# esp8285-router.net
KiCad netlist of a schematic drawn in EAGLE
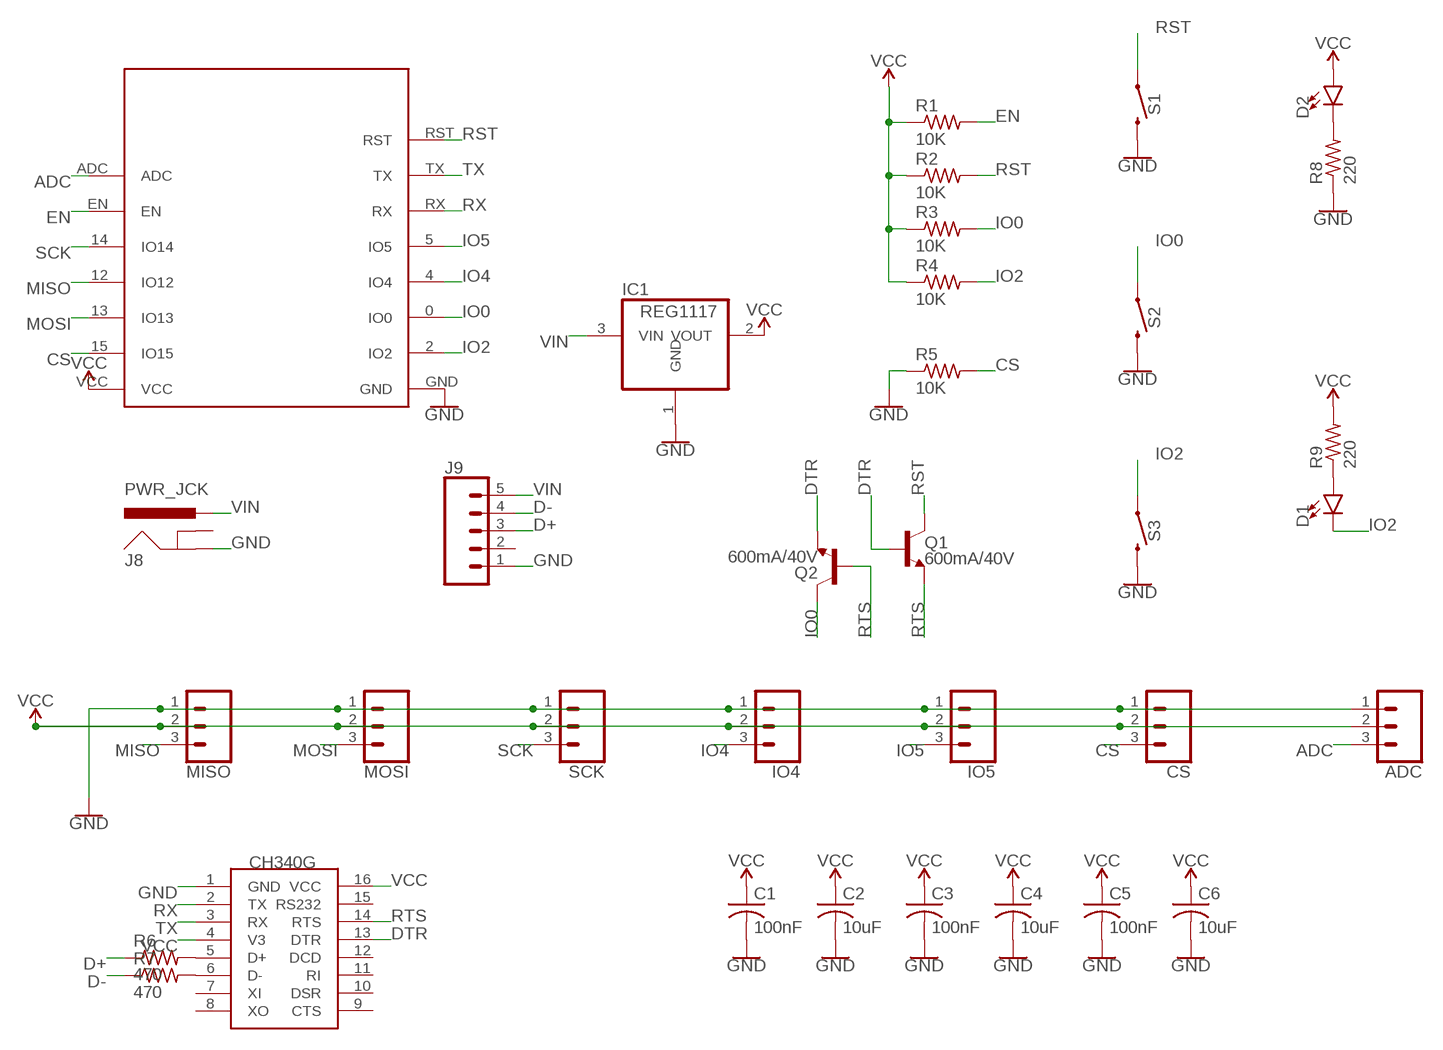
[diagram p0: schematic, sheet 1]

(export (version "E")
  (design (tool "Eeschema 10.0.6"))
  (components
    (comp (ref "ADC")
      (value "CONN_03")
      (footprint "eagle-import:1X03")
      (libsource (lib "eagle-import") (part "CONN_03"))
    )
    (comp (ref "C1")
      (value "100nF")
      (footprint "eagle-import:C1206")
      (libsource (lib "eagle-import") (part "C-USC1206"))
    )
    (comp (ref "C2")
      (value "10uF")
      (footprint "eagle-import:C1206")
      (libsource (lib "eagle-import") (part "C-USC1206"))
    )
    (comp (ref "C3")
      (value "100nF")
      (footprint "eagle-import:C1206")
      (libsource (lib "eagle-import") (part "C-USC1206"))
    )
    (comp (ref "C4")
      (value "10uF")
      (footprint "eagle-import:C1206")
      (libsource (lib "eagle-import") (part "C-USC1206"))
    )
    (comp (ref "C5")
      (value "100nF")
      (footprint "eagle-import:C1206")
      (libsource (lib "eagle-import") (part "C-USC1206"))
    )
    (comp (ref "C6")
      (value "10uF")
      (footprint "eagle-import:C1206")
      (libsource (lib "eagle-import") (part "C-USC1206"))
    )
    (comp (ref "CH340C")
      (value "CH340C")
      (footprint "eagle-import:SOIC16")
      (libsource (lib "eagle-import") (part "CH340G"))
    )
    (comp (ref "CS")
      (value "CONN_03")
      (footprint "eagle-import:1X03")
      (libsource (lib "eagle-import") (part "CONN_03"))
    )
    (comp (ref "D1")
      (value "LED1206")
      (footprint "eagle-import:LED-1206")
      (libsource (lib "eagle-import") (part "LED1206"))
    )
    (comp (ref "D2")
      (value "LED1206")
      (footprint "eagle-import:LED-1206")
      (libsource (lib "eagle-import") (part "LED1206"))
    )
    (comp (ref "IC1")
      (value "REG1117")
      (footprint "eagle-import:SOT223")
      (libsource (lib "eagle-import") (part "REG1117"))
    )
    (comp (ref "IO4")
      (value "CONN_03")
      (footprint "eagle-import:1X03")
      (libsource (lib "eagle-import") (part "CONN_03"))
    )
    (comp (ref "IO5")
      (value "CONN_03")
      (footprint "eagle-import:1X03")
      (libsource (lib "eagle-import") (part "CONN_03"))
    )
    (comp (ref "J8")
      (value "PWR_JCK")
      (footprint "eagle-import:POWER_JACK_SLOT")
      (libsource (lib "eagle-import") (part "POWER_JACKSLT"))
    )
    (comp (ref "J9")
      (value "CONN_05")
      (footprint "eagle-import:1X05")
      (libsource (lib "eagle-import") (part "CONN_05"))
    )
    (comp (ref "MISO")
      (value "CONN_03")
      (footprint "eagle-import:1X03")
      (libsource (lib "eagle-import") (part "CONN_03"))
    )
    (comp (ref "MOSI")
      (value "CONN_03")
      (footprint "eagle-import:1X03")
      (libsource (lib "eagle-import") (part "CONN_03"))
    )
    (comp (ref "Q1")
      (value "600mA/40V")
      (footprint "eagle-import:SOT23-3")
      (libsource (lib "eagle-import") (part "TRANS_NPN-MMBT2222AL"))
    )
    (comp (ref "Q2")
      (value "600mA/40V")
      (footprint "eagle-import:SOT23-3")
      (libsource (lib "eagle-import") (part "TRANS_NPN-MMBT2222AL"))
    )
    (comp (ref "R1")
      (value "10K")
      (footprint "eagle-import:R1206")
      (libsource (lib "eagle-import") (part "R-US_R1206"))
    )
    (comp (ref "R2")
      (value "10K")
      (footprint "eagle-import:R1206")
      (libsource (lib "eagle-import") (part "R-US_R1206"))
    )
    (comp (ref "R3")
      (value "10K")
      (footprint "eagle-import:R1206")
      (libsource (lib "eagle-import") (part "R-US_R1206"))
    )
    (comp (ref "R4")
      (value "10K")
      (footprint "eagle-import:R1206")
      (libsource (lib "eagle-import") (part "R-US_R1206"))
    )
    (comp (ref "R5")
      (value "10K")
      (footprint "eagle-import:R1206")
      (libsource (lib "eagle-import") (part "R-US_R1206"))
    )
    (comp (ref "R6")
      (value "470")
      (footprint "eagle-import:R1206")
      (libsource (lib "eagle-import") (part "R-US_R1206"))
    )
    (comp (ref "R7")
      (value "470")
      (footprint "eagle-import:R1206")
      (libsource (lib "eagle-import") (part "R-US_R1206"))
    )
    (comp (ref "R8")
      (value "220")
      (footprint "eagle-import:R1206")
      (libsource (lib "eagle-import") (part "R-US_R1206"))
    )
    (comp (ref "R9")
      (value "220")
      (footprint "eagle-import:R1206")
      (libsource (lib "eagle-import") (part "R-US_R1206"))
    )
    (comp (ref "S1")
      (value "MOMENTARY-SWITCH-SPST-PTH-6.0MM")
      (footprint "eagle-import:TACTILE_SWITCH_PTH_6.0MM")
      (libsource (lib "eagle-import") (part "MOMENTARY-SWITCH-SPST-PTH-6.0MM"))
    )
    (comp (ref "S2")
      (value "MOMENTARY-SWITCH-SPST-PTH-6.0MM")
      (footprint "eagle-import:TACTILE_SWITCH_PTH_6.0MM")
      (libsource (lib "eagle-import") (part "MOMENTARY-SWITCH-SPST-PTH-6.0MM"))
    )
    (comp (ref "S3")
      (value "MOMENTARY-SWITCH-SPST-PTH-6.0MM")
      (footprint "eagle-import:TACTILE_SWITCH_PTH_6.0MM")
      (libsource (lib "eagle-import") (part "MOMENTARY-SWITCH-SPST-PTH-6.0MM"))
    )
    (comp (ref "SCK")
      (value "CONN_03")
      (footprint "eagle-import:1X03")
      (libsource (lib "eagle-import") (part "CONN_03"))
    )
    (comp (ref "U$1")
      (value "ESP-M2")
      (footprint "eagle-import:ESP-M2")
      (libsource (lib "eagle-import") (part "ESP-M2"))
    )
  )
  (nets
    (net (code "1") (name "/ADC") (class "Default")
      (node (ref "ADC") (pin "3") (pinfunction "3_3") (pintype "passive"))
      (node (ref "U$1") (pin "ADC") (pinfunction "ADC_ADC") (pintype "bidirectional"))
    )
    (net (code "2") (name "/CS") (class "Default")
      (node (ref "CS") (pin "3") (pinfunction "3_3") (pintype "passive"))
      (node (ref "R5") (pin "2") (pinfunction "2_2") (pintype "passive"))
      (node (ref "U$1") (pin "15") (pinfunction "IO15_15") (pintype "bidirectional"))
    )
    (net (code "3") (name "/D+") (class "Default")
      (node (ref "J9") (pin "3") (pinfunction "3_3") (pintype "passive"))
      (node (ref "R6") (pin "1") (pinfunction "1_1") (pintype "passive"))
    )
    (net (code "4") (name "/D-") (class "Default")
      (node (ref "J9") (pin "4") (pinfunction "4_4") (pintype "passive"))
      (node (ref "R7") (pin "1") (pinfunction "1_1") (pintype "passive"))
    )
    (net (code "5") (name "/DTR") (class "Default")
      (node (ref "CH340C") (pin "13") (pinfunction "DTR_13") (pintype "bidirectional"))
      (node (ref "Q1") (pin "1") (pinfunction "B_1") (pintype "passive"))
      (node (ref "Q2") (pin "2") (pinfunction "E_2") (pintype "passive"))
    )
    (net (code "6") (name "/EN") (class "Default")
      (node (ref "R1") (pin "2") (pinfunction "2_2") (pintype "passive"))
      (node (ref "U$1") (pin "EN") (pinfunction "EN_EN") (pintype "bidirectional"))
    )
    (net (code "7") (name "/IO0") (class "Default")
      (node (ref "Q2") (pin "3") (pinfunction "C_3") (pintype "passive"))
      (node (ref "R3") (pin "2") (pinfunction "2_2") (pintype "passive"))
      (node (ref "S2") (pin "1") (pinfunction "1_1") (pintype "passive"))
      (node (ref "U$1") (pin "0") (pinfunction "IO0_0") (pintype "bidirectional"))
    )
    (net (code "8") (name "/IO2") (class "Default")
      (node (ref "D1") (pin "C") (pinfunction "C_C") (pintype "passive"))
      (node (ref "R4") (pin "2") (pinfunction "2_2") (pintype "passive"))
      (node (ref "S3") (pin "1") (pinfunction "1_1") (pintype "passive"))
      (node (ref "U$1") (pin "2") (pinfunction "IO2_2") (pintype "bidirectional"))
    )
    (net (code "9") (name "/IO4") (class "Default")
      (node (ref "IO4") (pin "3") (pinfunction "3_3") (pintype "passive"))
      (node (ref "U$1") (pin "4") (pinfunction "IO4_4") (pintype "bidirectional"))
    )
    (net (code "10") (name "/IO5") (class "Default")
      (node (ref "IO5") (pin "3") (pinfunction "3_3") (pintype "passive"))
      (node (ref "U$1") (pin "5") (pinfunction "IO5_5") (pintype "bidirectional"))
    )
    (net (code "11") (name "/MISO") (class "Default")
      (node (ref "MISO") (pin "3") (pinfunction "3_3") (pintype "passive"))
      (node (ref "U$1") (pin "12") (pinfunction "IO12_12") (pintype "bidirectional"))
    )
    (net (code "12") (name "/MOSI") (class "Default")
      (node (ref "MOSI") (pin "3") (pinfunction "3_3") (pintype "passive"))
      (node (ref "U$1") (pin "13") (pinfunction "IO13_13") (pintype "bidirectional"))
    )
    (net (code "13") (name "/RST") (class "Default")
      (node (ref "Q1") (pin "3") (pinfunction "C_3") (pintype "passive"))
      (node (ref "R2") (pin "2") (pinfunction "2_2") (pintype "passive"))
      (node (ref "S1") (pin "1") (pinfunction "1_1") (pintype "passive"))
      (node (ref "U$1") (pin "RST") (pinfunction "RST_RST") (pintype "bidirectional"))
    )
    (net (code "14") (name "/RTS") (class "Default")
      (node (ref "CH340C") (pin "14") (pinfunction "RTS_14") (pintype "bidirectional"))
      (node (ref "Q1") (pin "2") (pinfunction "E_2") (pintype "passive"))
      (node (ref "Q2") (pin "1") (pinfunction "B_1") (pintype "passive"))
    )
    (net (code "15") (name "/RX") (class "Default")
      (node (ref "CH340C") (pin "2") (pinfunction "TX_2") (pintype "bidirectional"))
      (node (ref "U$1") (pin "RX") (pinfunction "RX_RX") (pintype "bidirectional"))
    )
    (net (code "16") (name "/SCK") (class "Default")
      (node (ref "SCK") (pin "3") (pinfunction "3_3") (pintype "passive"))
      (node (ref "U$1") (pin "14") (pinfunction "IO14_14") (pintype "bidirectional"))
    )
    (net (code "17") (name "/TX") (class "Default")
      (node (ref "CH340C") (pin "3") (pinfunction "RX_3") (pintype "bidirectional"))
      (node (ref "U$1") (pin "TX") (pinfunction "TX_TX") (pintype "bidirectional"))
    )
    (net (code "18") (name "/VIN") (class "Default")
      (node (ref "IC1") (pin "3") (pinfunction "VIN_3") (pintype "input"))
      (node (ref "J8") (pin "PWR") (pinfunction "PWR_PWR") (pintype "bidirectional"))
      (node (ref "J9") (pin "5") (pinfunction "5_5") (pintype "passive"))
    )
    (net (code "19") (name "GND") (class "Default")
      (node (ref "ADC") (pin "1") (pinfunction "1_1") (pintype "passive"))
      (node (ref "C1") (pin "2") (pinfunction "2_2") (pintype "passive"))
      (node (ref "C2") (pin "2") (pinfunction "2_2") (pintype "passive"))
      (node (ref "C3") (pin "2") (pinfunction "2_2") (pintype "passive"))
      (node (ref "C4") (pin "2") (pinfunction "2_2") (pintype "passive"))
      (node (ref "C5") (pin "2") (pinfunction "2_2") (pintype "passive"))
      (node (ref "C6") (pin "2") (pinfunction "2_2") (pintype "passive"))
      (node (ref "CH340C") (pin "1") (pinfunction "GND_1") (pintype "bidirectional"))
      (node (ref "CS") (pin "1") (pinfunction "1_1") (pintype "passive"))
      (node (ref "IC1") (pin "1") (pinfunction "GND_1") (pintype "power_in"))
      (node (ref "IO4") (pin "1") (pinfunction "1_1") (pintype "passive"))
      (node (ref "IO5") (pin "1") (pinfunction "1_1") (pintype "passive"))
      (node (ref "J8") (pin "GND@2") (pinfunction "GND_GND@2") (pintype "bidirectional"))
      (node (ref "J9") (pin "1") (pinfunction "1_1") (pintype "passive"))
      (node (ref "MISO") (pin "1") (pinfunction "1_1") (pintype "passive"))
      (node (ref "MOSI") (pin "1") (pinfunction "1_1") (pintype "passive"))
      (node (ref "R5") (pin "1") (pinfunction "1_1") (pintype "passive"))
      (node (ref "R8") (pin "1") (pinfunction "1_1") (pintype "passive"))
      (node (ref "S1") (pin "3") (pinfunction "2_3") (pintype "passive"))
      (node (ref "S2") (pin "3") (pinfunction "2_3") (pintype "passive"))
      (node (ref "S3") (pin "3") (pinfunction "2_3") (pintype "passive"))
      (node (ref "SCK") (pin "1") (pinfunction "1_1") (pintype "passive"))
      (node (ref "U$1") (pin "GND") (pinfunction "GND_GND") (pintype "bidirectional"))
    )
    (net (code "20") (name "Net-(CH340C-D+)") (class "Default")
      (node (ref "CH340C") (pin "5") (pinfunction "D+_5") (pintype "bidirectional"))
      (node (ref "R6") (pin "2") (pinfunction "2_2") (pintype "passive"))
    )
    (net (code "21") (name "Net-(CH340C-D-)") (class "Default")
      (node (ref "CH340C") (pin "6") (pinfunction "D-_6") (pintype "bidirectional"))
      (node (ref "R7") (pin "2") (pinfunction "2_2") (pintype "passive"))
    )
    (net (code "22") (name "Net-(D1-PadA)") (class "Default")
      (node (ref "D1") (pin "A") (pinfunction "A_A") (pintype "passive"))
      (node (ref "R9") (pin "1") (pinfunction "1_1") (pintype "passive"))
    )
    (net (code "23") (name "Net-(D2-PadC)") (class "Default")
      (node (ref "D2") (pin "C") (pinfunction "C_C") (pintype "passive"))
      (node (ref "R8") (pin "2") (pinfunction "2_2") (pintype "passive"))
    )
    (net (code "24") (name "VCC") (class "Default")
      (node (ref "ADC") (pin "2") (pinfunction "2_2") (pintype "passive"))
      (node (ref "C1") (pin "1") (pinfunction "1_1") (pintype "passive"))
      (node (ref "C2") (pin "1") (pinfunction "1_1") (pintype "passive"))
      (node (ref "C3") (pin "1") (pinfunction "1_1") (pintype "passive"))
      (node (ref "C4") (pin "1") (pinfunction "1_1") (pintype "passive"))
      (node (ref "C5") (pin "1") (pinfunction "1_1") (pintype "passive"))
      (node (ref "C6") (pin "1") (pinfunction "1_1") (pintype "passive"))
      (node (ref "CH340C") (pin "16") (pinfunction "VCC_16") (pintype "bidirectional"))
      (node (ref "CH340C") (pin "4") (pinfunction "V3_4") (pintype "bidirectional"))
      (node (ref "CS") (pin "2") (pinfunction "2_2") (pintype "passive"))
      (node (ref "D2") (pin "A") (pinfunction "A_A") (pintype "passive"))
      (node (ref "IC1") (pin "2") (pinfunction "VOUT_2") (pintype "output"))
      (node (ref "IO4") (pin "2") (pinfunction "2_2") (pintype "passive"))
      (node (ref "IO5") (pin "2") (pinfunction "2_2") (pintype "passive"))
      (node (ref "MISO") (pin "2") (pinfunction "2_2") (pintype "passive"))
      (node (ref "MOSI") (pin "2") (pinfunction "2_2") (pintype "passive"))
      (node (ref "R1") (pin "1") (pinfunction "1_1") (pintype "passive"))
      (node (ref "R2") (pin "1") (pinfunction "1_1") (pintype "passive"))
      (node (ref "R3") (pin "1") (pinfunction "1_1") (pintype "passive"))
      (node (ref "R4") (pin "1") (pinfunction "1_1") (pintype "passive"))
      (node (ref "R9") (pin "2") (pinfunction "2_2") (pintype "passive"))
      (node (ref "SCK") (pin "2") (pinfunction "2_2") (pintype "passive"))
      (node (ref "U$1") (pin "VCC") (pinfunction "VCC_VCC") (pintype "bidirectional"))
    )
    (net (code "25") (name "unconnected-(CH340C-CTS-Pad9)") (class "Default")
      (node (ref "CH340C") (pin "9") (pinfunction "CTS_9") (pintype "bidirectional"))
    )
    (net (code "26") (name "unconnected-(CH340C-DCD-Pad12)") (class "Default")
      (node (ref "CH340C") (pin "12") (pinfunction "DCD_12") (pintype "bidirectional"))
    )
    (net (code "27") (name "unconnected-(CH340C-DSR-Pad10)") (class "Default")
      (node (ref "CH340C") (pin "10") (pinfunction "DSR_10") (pintype "bidirectional"))
    )
    (net (code "28") (name "unconnected-(CH340C-RI-Pad11)") (class "Default")
      (node (ref "CH340C") (pin "11") (pinfunction "RI_11") (pintype "bidirectional"))
    )
    (net (code "29") (name "unconnected-(CH340C-RS232-Pad15)") (class "Default")
      (node (ref "CH340C") (pin "15") (pinfunction "RS232_15") (pintype "bidirectional"))
    )
    (net (code "30") (name "unconnected-(CH340C-XI-Pad7)") (class "Default")
      (node (ref "CH340C") (pin "7") (pinfunction "XI_7") (pintype "bidirectional"))
    )
    (net (code "31") (name "unconnected-(CH340C-XO-Pad8)") (class "Default")
      (node (ref "CH340C") (pin "8") (pinfunction "XO_8") (pintype "bidirectional"))
    )
    (net (code "32") (name "unconnected-(J8-GNDBREAK-PadGND@1)") (class "Default")
      (node (ref "J8") (pin "GND@1") (pinfunction "GNDBREAK_GND@1") (pintype "bidirectional"))
    )
    (net (code "33") (name "unconnected-(J9-Pad2)") (class "Default")
      (node (ref "J9") (pin "2") (pinfunction "2_2") (pintype "passive"))
    )
  )
)
